# Gesture.net
KiCad netlist of a schematic drawn in EAGLE
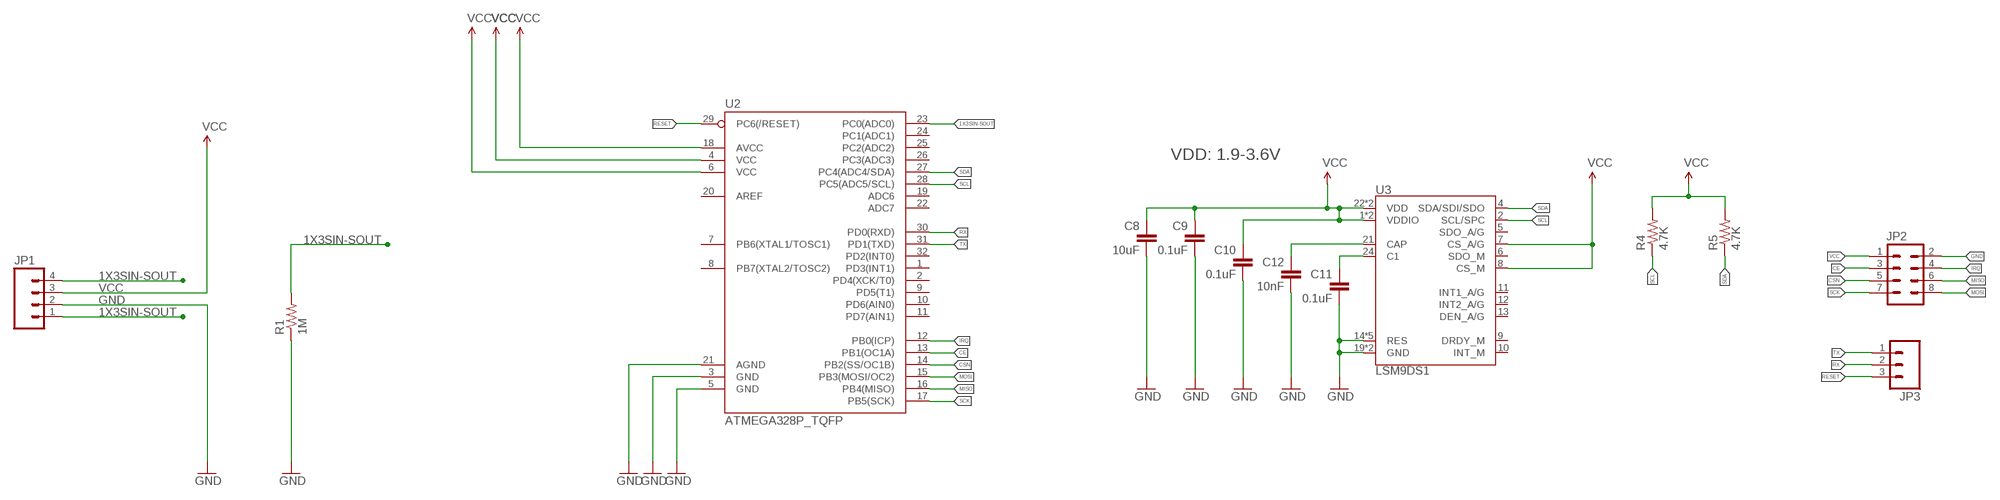
[diagram p0: schematic, sheet 1]

(export (version "E")
  (design (tool "Eeschema 10.0.6"))
  (components
    (comp (ref "C8")
      (value "10uF")
      (footprint "eagle-import:0603-CAP")
      (libsource (lib "eagle-import") (part "10UF-6.3V-20%(0603)"))
    )
    (comp (ref "C9")
      (value "0.1uF")
      (footprint "eagle-import:0603-CAP")
      (libsource (lib "eagle-import") (part "0.1UF-25V(+80/-20%)(0603)"))
    )
    (comp (ref "C10")
      (value "0.1uF")
      (footprint "eagle-import:0603-CAP")
      (libsource (lib "eagle-import") (part "0.1UF-25V(+80/-20%)(0603)"))
    )
    (comp (ref "C11")
      (value "0.1uF")
      (footprint "eagle-import:0603-CAP")
      (libsource (lib "eagle-import") (part "0.1UF-25V(+80/-20%)(0603)"))
    )
    (comp (ref "C12")
      (value "10nF")
      (footprint "eagle-import:0603-CAP")
      (libsource (lib "eagle-import") (part "10NF/10000PF-50V-10%(0603)"))
    )
    (comp (ref "JP1")
      (value "M04PTH")
      (footprint "eagle-import:1X04")
      (libsource (lib "eagle-import") (part "M04PTH"))
    )
    (comp (ref "JP2")
      (value "M04X2_0.05\"")
      (footprint "eagle-import:M04X2_0.05_")
      (libsource (lib "eagle-import") (part "M04X2_0.05{dblquote}"))
    )
    (comp (ref "JP3")
      (value "M03PTH")
      (footprint "eagle-import:1X03")
      (libsource (lib "eagle-import") (part "M03PTH"))
    )
    (comp (ref "R1")
      (value "1M")
      (footprint "eagle-import:R0603")
      (libsource (lib "eagle-import") (part "R-US_R0603"))
    )
    (comp (ref "R4")
      (value "4.7K")
      (footprint "eagle-import:0603-RES")
      (libsource (lib "eagle-import") (part "4.7KOHM-1/10W-1%(0603)"))
    )
    (comp (ref "R5")
      (value "4.7K")
      (footprint "eagle-import:0603-RES")
      (libsource (lib "eagle-import") (part "4.7KOHM-1/10W-1%(0603)"))
    )
    (comp (ref "U2")
      (value "ATMEGA328P_TQFP")
      (footprint "eagle-import:TQFP32-08")
      (libsource (lib "eagle-import") (part "ATMEGA328P_TQFP"))
    )
    (comp (ref "U3")
      (value "LSM9DS1")
      (footprint "eagle-import:LGA24-8X4")
      (libsource (lib "eagle-import") (part "LSM9DS1"))
    )
  )
  (nets
    (net (code "1") (name "1X3SIN-SOUT") (class "Default")
      (node (ref "JP1") (pin "1") (pinfunction "1_1") (pintype "passive"))
      (node (ref "JP1") (pin "4") (pinfunction "4_4") (pintype "passive"))
      (node (ref "R1") (pin "2") (pinfunction "2_2") (pintype "passive"))
      (node (ref "U2") (pin "23") (pinfunction "PC0(ADC0)_23") (pintype "bidirectional"))
    )
    (net (code "2") (name "CE") (class "Default")
      (node (ref "JP2") (pin "3") (pinfunction "3_3") (pintype "passive"))
      (node (ref "U2") (pin "13") (pinfunction "PB1(OC1A)_13") (pintype "bidirectional"))
    )
    (net (code "3") (name "CSN") (class "Default")
      (node (ref "JP2") (pin "5") (pinfunction "5_5") (pintype "passive"))
      (node (ref "U2") (pin "14") (pinfunction "PB2(SS/OC1B)_14") (pintype "bidirectional"))
    )
    (net (code "4") (name "GND") (class "Default")
      (node (ref "C10") (pin "2") (pinfunction "2_2") (pintype "passive"))
      (node (ref "C11") (pin "2") (pinfunction "2_2") (pintype "passive"))
      (node (ref "C12") (pin "2") (pinfunction "2_2") (pintype "passive"))
      (node (ref "C8") (pin "2") (pinfunction "2_2") (pintype "passive"))
      (node (ref "C9") (pin "2") (pinfunction "2_2") (pintype "passive"))
      (node (ref "JP1") (pin "2") (pinfunction "2_2") (pintype "passive"))
      (node (ref "JP2") (pin "2") (pinfunction "2_2") (pintype "passive"))
      (node (ref "R1") (pin "1") (pinfunction "1_1") (pintype "passive"))
      (node (ref "U2") (pin "21") (pinfunction "AGND_21") (pintype "bidirectional"))
      (node (ref "U2") (pin "3") (pinfunction "GND_3") (pintype "bidirectional"))
      (node (ref "U2") (pin "5") (pinfunction "GND_5") (pintype "bidirectional"))
      (node (ref "U3") (pin "14") (pinfunction "RES_14") (pintype "bidirectional"))
      (node (ref "U3") (pin "15") (pinfunction "RES_15") (pintype "bidirectional"))
      (node (ref "U3") (pin "16") (pinfunction "RES_16") (pintype "bidirectional"))
      (node (ref "U3") (pin "17") (pinfunction "RES_17") (pintype "bidirectional"))
      (node (ref "U3") (pin "18") (pinfunction "RES_18") (pintype "bidirectional"))
      (node (ref "U3") (pin "19") (pinfunction "GND_19") (pintype "bidirectional"))
      (node (ref "U3") (pin "20") (pinfunction "GND_20") (pintype "bidirectional"))
    )
    (net (code "5") (name "IRQ") (class "Default")
      (node (ref "JP2") (pin "4") (pinfunction "4_4") (pintype "passive"))
      (node (ref "U2") (pin "12") (pinfunction "PB0(ICP)_12") (pintype "bidirectional"))
    )
    (net (code "6") (name "MISO") (class "Default")
      (node (ref "JP2") (pin "6") (pinfunction "6_6") (pintype "passive"))
      (node (ref "U2") (pin "16") (pinfunction "PB4(MISO)_16") (pintype "bidirectional"))
    )
    (net (code "7") (name "MOSI") (class "Default")
      (node (ref "JP2") (pin "8") (pinfunction "8_8") (pintype "passive"))
      (node (ref "U2") (pin "15") (pinfunction "PB3(MOSI/OC2)_15") (pintype "bidirectional"))
    )
    (net (code "8") (name "Net-(U3-C1)") (class "Default")
      (node (ref "C11") (pin "1") (pinfunction "1_1") (pintype "passive"))
      (node (ref "U3") (pin "24") (pinfunction "C1_24") (pintype "bidirectional"))
    )
    (net (code "9") (name "Net-(U3-CAP)") (class "Default")
      (node (ref "C12") (pin "1") (pinfunction "1_1") (pintype "passive"))
      (node (ref "U3") (pin "21") (pinfunction "CAP_21") (pintype "bidirectional"))
    )
    (net (code "10") (name "RESET") (class "Default")
      (node (ref "JP3") (pin "3") (pinfunction "3_3") (pintype "passive"))
      (node (ref "U2") (pin "29") (pinfunction "PC6(/RESET)_29") (pintype "bidirectional"))
    )
    (net (code "11") (name "RX") (class "Default")
      (node (ref "JP3") (pin "2") (pinfunction "2_2") (pintype "passive"))
      (node (ref "U2") (pin "30") (pinfunction "PD0(RXD)_30") (pintype "bidirectional"))
    )
    (net (code "12") (name "SCK") (class "Default")
      (node (ref "JP2") (pin "7") (pinfunction "7_7") (pintype "passive"))
      (node (ref "U2") (pin "17") (pinfunction "PB5(SCK)_17") (pintype "bidirectional"))
    )
    (net (code "13") (name "SCL") (class "Default")
      (node (ref "R4") (pin "1") (pinfunction "1_1") (pintype "passive"))
      (node (ref "U2") (pin "28") (pinfunction "PC5(ADC5/SCL)_28") (pintype "bidirectional"))
      (node (ref "U3") (pin "2") (pinfunction "SCL/SPC_2") (pintype "bidirectional"))
    )
    (net (code "14") (name "SDA") (class "Default")
      (node (ref "R5") (pin "1") (pinfunction "1_1") (pintype "passive"))
      (node (ref "U2") (pin "27") (pinfunction "PC4(ADC4/SDA)_27") (pintype "bidirectional"))
      (node (ref "U3") (pin "4") (pinfunction "SDA/SDI/SDO_4") (pintype "bidirectional"))
    )
    (net (code "15") (name "TX") (class "Default")
      (node (ref "JP3") (pin "1") (pinfunction "1_1") (pintype "passive"))
      (node (ref "U2") (pin "31") (pinfunction "PD1(TXD)_31") (pintype "bidirectional"))
    )
    (net (code "16") (name "VCC") (class "Default")
      (node (ref "C10") (pin "1") (pinfunction "1_1") (pintype "passive"))
      (node (ref "C8") (pin "1") (pinfunction "1_1") (pintype "passive"))
      (node (ref "C9") (pin "1") (pinfunction "1_1") (pintype "passive"))
      (node (ref "JP1") (pin "3") (pinfunction "3_3") (pintype "passive"))
      (node (ref "JP2") (pin "1") (pinfunction "1_1") (pintype "passive"))
      (node (ref "R4") (pin "2") (pinfunction "2_2") (pintype "passive"))
      (node (ref "R5") (pin "2") (pinfunction "2_2") (pintype "passive"))
      (node (ref "U2") (pin "18") (pinfunction "AVCC_18") (pintype "bidirectional"))
      (node (ref "U2") (pin "4") (pinfunction "VCC_4") (pintype "bidirectional"))
      (node (ref "U2") (pin "6") (pinfunction "VCC_6") (pintype "bidirectional"))
      (node (ref "U3") (pin "1") (pinfunction "VDDIO_1") (pintype "bidirectional"))
      (node (ref "U3") (pin "22") (pinfunction "VDD_22") (pintype "bidirectional"))
      (node (ref "U3") (pin "23") (pinfunction "VDD_23") (pintype "bidirectional"))
      (node (ref "U3") (pin "3") (pinfunction "VDDIO_3") (pintype "bidirectional"))
      (node (ref "U3") (pin "7") (pinfunction "CS_A/G_7") (pintype "bidirectional"))
      (node (ref "U3") (pin "8") (pinfunction "CS_M_8") (pintype "bidirectional"))
    )
    (net (code "17") (name "unconnected-(U2-ADC6-Pad19)") (class "Default")
      (node (ref "U2") (pin "19") (pinfunction "ADC6_19") (pintype "bidirectional"))
    )
    (net (code "18") (name "unconnected-(U2-ADC7-Pad22)") (class "Default")
      (node (ref "U2") (pin "22") (pinfunction "ADC7_22") (pintype "bidirectional"))
    )
    (net (code "19") (name "unconnected-(U2-AREF-Pad20)") (class "Default")
      (node (ref "U2") (pin "20") (pinfunction "AREF_20") (pintype "bidirectional"))
    )
    (net (code "20") (name "unconnected-(U2-PB6(XTAL1{slash}TOSC1)-Pad7)") (class "Default")
      (node (ref "U2") (pin "7") (pinfunction "PB6(XTAL1/TOSC1)_7") (pintype "bidirectional"))
    )
    (net (code "21") (name "unconnected-(U2-PB7(XTAL2{slash}TOSC2)-Pad8)") (class "Default")
      (node (ref "U2") (pin "8") (pinfunction "PB7(XTAL2/TOSC2)_8") (pintype "bidirectional"))
    )
    (net (code "22") (name "unconnected-(U2-PC1(ADC1)-Pad24)") (class "Default")
      (node (ref "U2") (pin "24") (pinfunction "PC1(ADC1)_24") (pintype "bidirectional"))
    )
    (net (code "23") (name "unconnected-(U2-PC2(ADC2)-Pad25)") (class "Default")
      (node (ref "U2") (pin "25") (pinfunction "PC2(ADC2)_25") (pintype "bidirectional"))
    )
    (net (code "24") (name "unconnected-(U2-PC3(ADC3)-Pad26)") (class "Default")
      (node (ref "U2") (pin "26") (pinfunction "PC3(ADC3)_26") (pintype "bidirectional"))
    )
    (net (code "25") (name "unconnected-(U2-PD2(INT0)-Pad32)") (class "Default")
      (node (ref "U2") (pin "32") (pinfunction "PD2(INT0)_32") (pintype "bidirectional"))
    )
    (net (code "26") (name "unconnected-(U2-PD3(INT1)-Pad1)") (class "Default")
      (node (ref "U2") (pin "1") (pinfunction "PD3(INT1)_1") (pintype "bidirectional"))
    )
    (net (code "27") (name "unconnected-(U2-PD4(XCK{slash}T0)-Pad2)") (class "Default")
      (node (ref "U2") (pin "2") (pinfunction "PD4(XCK/T0)_2") (pintype "bidirectional"))
    )
    (net (code "28") (name "unconnected-(U2-PD5(T1)-Pad9)") (class "Default")
      (node (ref "U2") (pin "9") (pinfunction "PD5(T1)_9") (pintype "bidirectional"))
    )
    (net (code "29") (name "unconnected-(U2-PD6(AIN0)-Pad10)") (class "Default")
      (node (ref "U2") (pin "10") (pinfunction "PD6(AIN0)_10") (pintype "bidirectional"))
    )
    (net (code "30") (name "unconnected-(U2-PD7(AIN1)-Pad11)") (class "Default")
      (node (ref "U2") (pin "11") (pinfunction "PD7(AIN1)_11") (pintype "bidirectional"))
    )
    (net (code "31") (name "unconnected-(U3-DEN_A{slash}G-Pad13)") (class "Default")
      (node (ref "U3") (pin "13") (pinfunction "DEN_A/G_13") (pintype "bidirectional"))
    )
    (net (code "32") (name "unconnected-(U3-DRDY_M-Pad9)") (class "Default")
      (node (ref "U3") (pin "9") (pinfunction "DRDY_M_9") (pintype "bidirectional"))
    )
    (net (code "33") (name "unconnected-(U3-INT1_A{slash}G-Pad11)") (class "Default")
      (node (ref "U3") (pin "11") (pinfunction "INT1_A/G_11") (pintype "bidirectional"))
    )
    (net (code "34") (name "unconnected-(U3-INT2_A{slash}G-Pad12)") (class "Default")
      (node (ref "U3") (pin "12") (pinfunction "INT2_A/G_12") (pintype "bidirectional"))
    )
    (net (code "35") (name "unconnected-(U3-INT_M-Pad10)") (class "Default")
      (node (ref "U3") (pin "10") (pinfunction "INT_M_10") (pintype "bidirectional"))
    )
    (net (code "36") (name "unconnected-(U3-SDO_A{slash}G-Pad5)") (class "Default")
      (node (ref "U3") (pin "5") (pinfunction "SDO_A/G_5") (pintype "bidirectional"))
    )
    (net (code "37") (name "unconnected-(U3-SDO_M-Pad6)") (class "Default")
      (node (ref "U3") (pin "6") (pinfunction "SDO_M_6") (pintype "bidirectional"))
    )
  )
)
